# first_schematic.net
KiCad netlist of a schematic drawn in EAGLE
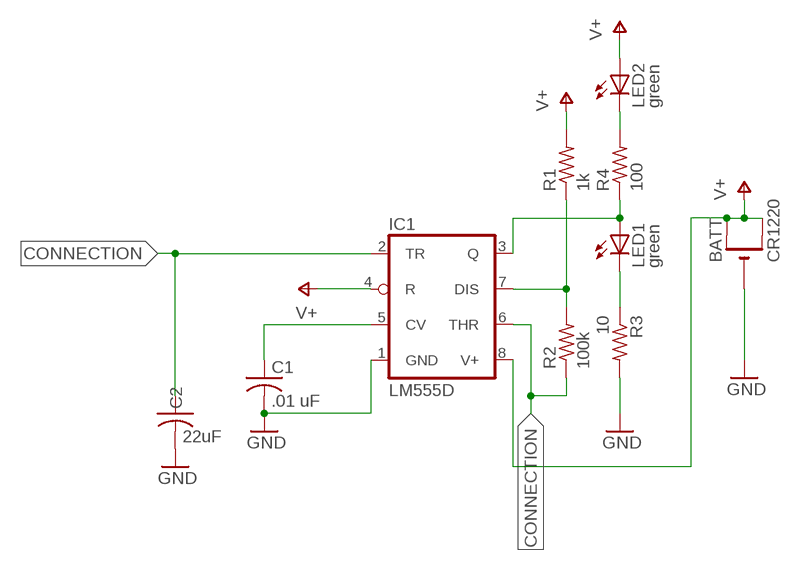
[diagram p0: schematic, sheet 1]

(export (version "E")
  (design (tool "Eeschema 10.0.6"))
  (components
    (comp (ref "BATT")
      (value "CR1220")
      (footprint "eagle-import:CR1220-SMD")
      (libsource (lib "eagle-import") (part "CR1220SMT"))
    )
    (comp (ref "C1")
      (value ".01 uF")
      (footprint "eagle-import:C0805")
      (fields (field (name "MF") "KEMET") (field (name "MPN") "CDR31BX103AKZS"))
      (libsource (lib "eagle-import") (part "C-USC0805"))
    )
    (comp (ref "C2")
      (value "22uF")
      (footprint "eagle-import:C0805")
      (libsource (lib "eagle-import") (part "C-USC0805"))
    )
    (comp (ref "IC1")
      (value "LM555D")
      (footprint "eagle-import:SO08")
      (libsource (lib "eagle-import") (part "555DLM"))
    )
    (comp (ref "LED1")
      (value "green")
      (footprint "eagle-import:CHIPLED_0805")
      (libsource (lib "eagle-import") (part "LEDCHIPLED_0805"))
    )
    (comp (ref "LED2")
      (value "green")
      (footprint "eagle-import:CHIPLED_0805")
      (libsource (lib "eagle-import") (part "LEDCHIPLED_0805"))
    )
    (comp (ref "R1")
      (value "1k")
      (footprint "eagle-import:R0805")
      (libsource (lib "eagle-import") (part "R-US_R0805"))
    )
    (comp (ref "R2")
      (value "100k")
      (footprint "eagle-import:R0805")
      (libsource (lib "eagle-import") (part "R-US_R0805"))
    )
    (comp (ref "R3")
      (value "10")
      (footprint "eagle-import:R0805")
      (libsource (lib "eagle-import") (part "R-US_R0805"))
    )
    (comp (ref "R4")
      (value "100")
      (footprint "eagle-import:R0805")
      (libsource (lib "eagle-import") (part "R-US_R0805"))
    )
  )
  (nets
    (net (code "1") (name "CONNECTION") (class "Default")
      (node (ref "C2") (pin "1") (pinfunction "1_1") (pintype "passive"))
      (node (ref "IC1") (pin "2") (pinfunction "TR_2") (pintype "input"))
      (node (ref "IC1") (pin "6") (pinfunction "THR_6") (pintype "input"))
      (node (ref "R2") (pin "1") (pinfunction "1_1") (pintype "passive"))
    )
    (net (code "2") (name "GND") (class "Default")
      (node (ref "BATT") (pin "-") (pinfunction "-_-") (pintype "passive"))
      (node (ref "C1") (pin "2") (pinfunction "2_2") (pintype "passive"))
      (node (ref "C2") (pin "2") (pinfunction "2_2") (pintype "passive"))
      (node (ref "IC1") (pin "1") (pinfunction "GND_1") (pintype "power_in"))
      (node (ref "R3") (pin "2") (pinfunction "2_2") (pintype "passive"))
    )
    (net (code "3") (name "Net-(IC1-CV)") (class "Default")
      (node (ref "C1") (pin "1") (pinfunction "1_1") (pintype "passive"))
      (node (ref "IC1") (pin "5") (pinfunction "CV_5") (pintype "input"))
    )
    (net (code "4") (name "Net-(IC1-DIS)") (class "Default")
      (node (ref "IC1") (pin "7") (pinfunction "DIS_7") (pintype "input"))
      (node (ref "R1") (pin "1") (pinfunction "1_1") (pintype "passive"))
      (node (ref "R2") (pin "2") (pinfunction "2_2") (pintype "passive"))
    )
    (net (code "5") (name "Net-(IC1-Q)") (class "Default")
      (node (ref "IC1") (pin "3") (pinfunction "Q_3") (pintype "output"))
      (node (ref "LED1") (pin "A") (pinfunction "A_A") (pintype "passive"))
      (node (ref "R4") (pin "1") (pinfunction "1_1") (pintype "passive"))
    )
    (net (code "6") (name "Net-(LED1-PadC)") (class "Default")
      (node (ref "LED1") (pin "C") (pinfunction "C_C") (pintype "passive"))
      (node (ref "R3") (pin "1") (pinfunction "1_1") (pintype "passive"))
    )
    (net (code "7") (name "Net-(LED2-PadC)") (class "Default")
      (node (ref "LED2") (pin "C") (pinfunction "C_C") (pintype "passive"))
      (node (ref "R4") (pin "2") (pinfunction "2_2") (pintype "passive"))
    )
    (net (code "8") (name "V+") (class "Default")
      (node (ref "BATT") (pin "+$1") (pinfunction "+_+$1") (pintype "passive"))
      (node (ref "BATT") (pin "+$2") (pinfunction "+1_+$2") (pintype "passive"))
      (node (ref "IC1") (pin "4") (pinfunction "R_4") (pintype "input"))
      (node (ref "IC1") (pin "8") (pinfunction "V+_8") (pintype "power_in"))
      (node (ref "LED2") (pin "A") (pinfunction "A_A") (pintype "passive"))
      (node (ref "R1") (pin "2") (pinfunction "2_2") (pintype "passive"))
    )
  )
)
